# BMS-Shem-v1.net
KiCad netlist of a schematic drawn in Altium Designer
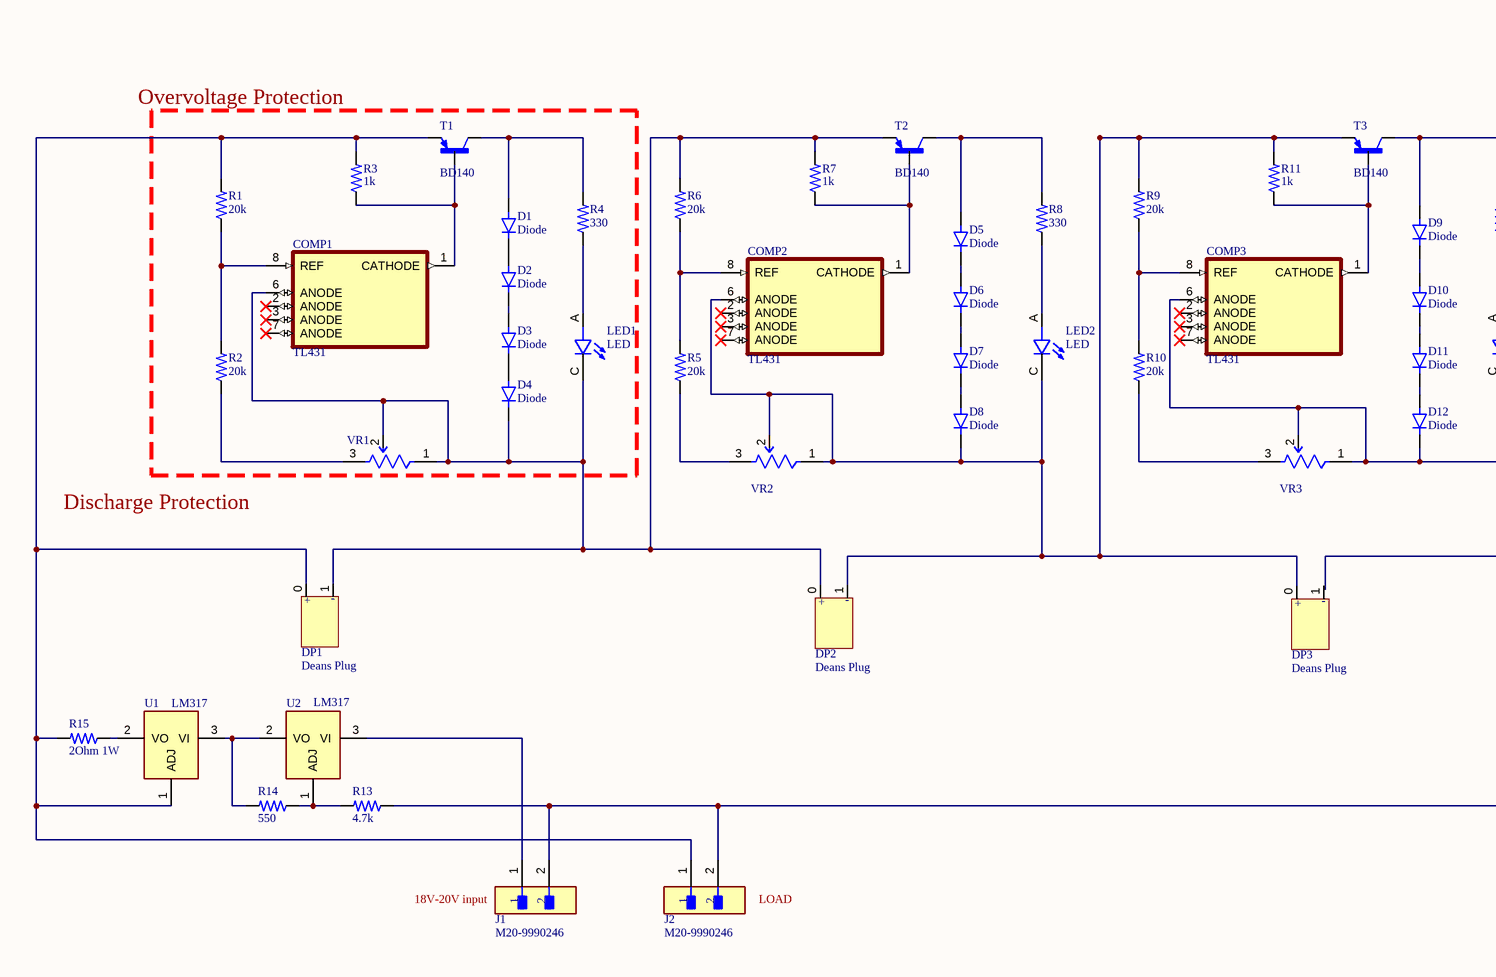
[diagram p0: BMS-Shem-v1.SchDoc, left]
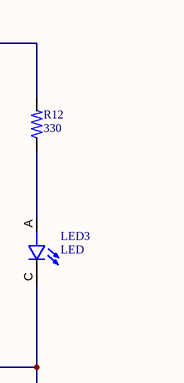
[diagram p1: BMS-Shem-v1.SchDoc, right]

(export (version "E")
  (design (tool "Eeschema 10.0.6"))
  (components
    (comp (ref "COMP1")
      (value "TL431")
      (footprint "SOIC127P599X175-8N")
      (description "Adjustable precision shunt regulator 8-SOIC 0 to 70")
      (fields (field (name "MF") "Texas Instruments") (field (name "MP") "TL431CD"))
      (libsource (lib "Schlib") (part "TL431"))
    )
    (comp (ref "COMP2")
      (value "TL431")
      (footprint "SOIC127P599X175-8N:SOIC127P599X175-8N")
      (description "Adjustable precision shunt regulator 8-SOIC 0 to 70")
      (fields (field (name "MF") "Texas Instruments") (field (name "MP") "TL431CD"))
      (libsource (lib "Schlib") (part "TL431"))
    )
    (comp (ref "COMP3")
      (value "TL431")
      (footprint "SOIC127P599X175-8N:SOIC127P599X175-8N")
      (description "Adjustable precision shunt regulator 8-SOIC 0 to 70")
      (fields (field (name "MF") "Texas Instruments") (field (name "MP") "TL431CD"))
      (libsource (lib "Schlib") (part "TL431"))
    )
    (comp (ref "D1")
      (value "Diode")
      (footprint "DIOAD1060W80L520D270")
      (description "Diode Standard 1000V 1A Through Hole DO-204AL _DO-41_")
      (fields (field (name "MF") "ON Semiconductor") (field (name "MP") "1N4007"))
      (libsource (lib "Schlib") (part "Diode"))
    )
    (comp (ref "D2")
      (value "Diode")
      (footprint "DIOAD1060W80L520D270")
      (description "Diode Standard 1000V 1A Through Hole DO-204AL _DO-41_")
      (fields (field (name "MF") "ON Semiconductor") (field (name "MP") "1N4007"))
      (libsource (lib "Schlib") (part "Diode"))
    )
    (comp (ref "D3")
      (value "Diode")
      (footprint "DIOAD1060W80L520D270")
      (description "Diode Standard 1000V 1A Through Hole DO-204AL _DO-41_")
      (fields (field (name "MF") "ON Semiconductor") (field (name "MP") "1N4007"))
      (libsource (lib "Schlib") (part "Diode"))
    )
    (comp (ref "D4")
      (value "Diode")
      (footprint "DIOAD1060W80L520D270")
      (description "Diode Standard 1000V 1A Through Hole DO-204AL _DO-41_")
      (fields (field (name "MF") "ON Semiconductor") (field (name "MP") "1N4007"))
      (libsource (lib "Schlib") (part "Diode"))
    )
    (comp (ref "D5")
      (value "Diode")
      (footprint "SnapEDApcb:DIOAD1060W80L520D270")
      (description "Diode Standard 1000V 1A Through Hole DO-204AL _DO-41_")
      (fields (field (name "MF") "ON Semiconductor") (field (name "MP") "1N4007"))
      (libsource (lib "Schlib") (part "Diode"))
    )
    (comp (ref "D6")
      (value "Diode")
      (footprint "SnapEDApcb:DIOAD1060W80L520D270")
      (description "Diode Standard 1000V 1A Through Hole DO-204AL _DO-41_")
      (fields (field (name "MF") "ON Semiconductor") (field (name "MP") "1N4007"))
      (libsource (lib "Schlib") (part "Diode"))
    )
    (comp (ref "D7")
      (value "Diode")
      (footprint "SnapEDApcb:DIOAD1060W80L520D270")
      (description "Diode Standard 1000V 1A Through Hole DO-204AL _DO-41_")
      (fields (field (name "MF") "ON Semiconductor") (field (name "MP") "1N4007"))
      (libsource (lib "Schlib") (part "Diode"))
    )
    (comp (ref "D8")
      (value "Diode")
      (footprint "SnapEDApcb:DIOAD1060W80L520D270")
      (description "Diode Standard 1000V 1A Through Hole DO-204AL _DO-41_")
      (fields (field (name "MF") "ON Semiconductor") (field (name "MP") "1N4007"))
      (libsource (lib "Schlib") (part "Diode"))
    )
    (comp (ref "D9")
      (value "Diode")
      (footprint "SnapEDApcb:DIOAD1060W80L520D270")
      (description "Diode Standard 1000V 1A Through Hole DO-204AL _DO-41_")
      (fields (field (name "MF") "ON Semiconductor") (field (name "MP") "1N4007"))
      (libsource (lib "Schlib") (part "Diode"))
    )
    (comp (ref "D10")
      (value "Diode")
      (footprint "SnapEDApcb:DIOAD1060W80L520D270")
      (description "Diode Standard 1000V 1A Through Hole DO-204AL _DO-41_")
      (fields (field (name "MF") "ON Semiconductor") (field (name "MP") "1N4007"))
      (libsource (lib "Schlib") (part "Diode"))
    )
    (comp (ref "D11")
      (value "Diode")
      (footprint "SnapEDApcb:DIOAD1060W80L520D270")
      (description "Diode Standard 1000V 1A Through Hole DO-204AL _DO-41_")
      (fields (field (name "MF") "ON Semiconductor") (field (name "MP") "1N4007"))
      (libsource (lib "Schlib") (part "Diode"))
    )
    (comp (ref "D12")
      (value "Diode")
      (footprint "SnapEDApcb:DIOAD1060W80L520D270")
      (description "Diode Standard 1000V 1A Through Hole DO-204AL _DO-41_")
      (fields (field (name "MF") "ON Semiconductor") (field (name "MP") "1N4007"))
      (libsource (lib "Schlib") (part "Diode"))
    )
    (comp (ref "DP1") (value "Deans Plug") (libsource (lib "Schlib") (part "Deans Plug")))
    (comp (ref "DP2") (value "Deans Plug") (libsource (lib "Schlib") (part "Deans Plug")))
    (comp (ref "DP3") (value "Deans Plug") (libsource (lib "Schlib") (part "Deans Plug")))
    (comp (ref "J1")
      (value "M20-9990246")
      (footprint "FP-M20-9990246-MFG")
      (description "CONN HEADER VERT 2POS 2.54MM")
      (fields
        (field (name "OCTOPART") "https://octopart.com/m20-9990246-harwin-2590635")
        (field (name "MANUFACTURER") "Harwin")
      )
      (libsource (lib "Altium Content Vault") (part "3bc925449376181038e59eaffc5286c"))
    )
    (comp (ref "J2")
      (value "M20-9990246")
      (footprint "FP-M20-9990246-MFG")
      (description "CONN HEADER VERT 2POS 2.54MM")
      (fields
        (field (name "OCTOPART") "https://octopart.com/m20-9990246-harwin-2590635")
        (field (name "MANUFACTURER") "Harwin")
      )
      (libsource (lib "Altium Content Vault") (part "3bc925449376181038e59eaffc5286c"))
    )
    (comp (ref "LED1")
      (value "LED")
      (footprint "SnapEDApcb:LED_151054RS03000")
      (description "Red 623nm LED Indication - Discrete 1.9V Radial")
      (fields (field (name "MF") "Wurth Electronics") (field (name "MP") "151054RS03000"))
      (libsource (lib "Schlib") (part "LED"))
    )
    (comp (ref "LED2")
      (value "LED")
      (footprint "SnapEDApcb:LED_151054RS03000")
      (description "Red 623nm LED Indication - Discrete 1.9V Radial")
      (fields (field (name "MF") "Wurth Electronics") (field (name "MP") "151054RS03000"))
      (libsource (lib "Schlib") (part "LED"))
    )
    (comp (ref "LED3")
      (value "LED")
      (footprint "SnapEDApcb:LED_151054RS03000")
      (description "Red 623nm LED Indication - Discrete 1.9V Radial")
      (fields (field (name "MF") "Wurth Electronics") (field (name "MP") "151054RS03000"))
      (libsource (lib "Schlib") (part "LED"))
    )
    (comp (ref "R1")
      (value "20k")
      (footprint "RESC2012X65N")
      (description "RES 20k OHM 1% 1/4W 0805")
      (fields (field (name "MF") "TE Connectivity") (field (name "TOLERANCE") "1%"))
      (libsource (lib "Schlib") (part "Resistor"))
    )
    (comp (ref "R2")
      (value "20k")
      (footprint "RESC2012X65N")
      (description "RES 20k OHM 1% 1/4W 0805")
      (fields (field (name "MF") "TE Connectivity") (field (name "TOLERANCE") "1%"))
      (libsource (lib "Schlib") (part "Resistor"))
    )
    (comp (ref "R3")
      (value "1k")
      (footprint "RESC2012X65N")
      (description "RES 1k OHM 1% 1/4W 0805")
      (fields (field (name "MF") "TE Connectivity") (field (name "TOLERANCE") "1%"))
      (libsource (lib "Schlib") (part "Resistor"))
    )
    (comp (ref "R4")
      (value "330")
      (footprint "SnapEDApcb:RESC2012X65N")
      (description "RES 330 OHM 1% 1/4W 0805")
      (fields (field (name "MF") "TE Connectivity") (field (name "TOLERANCE") "1%"))
      (libsource (lib "Schlib") (part "Resistor"))
    )
    (comp (ref "R5")
      (value "20k")
      (footprint "RESC2012X65N")
      (description "RES 20k OHM 1% 1/4W 0805")
      (fields (field (name "MF") "TE Connectivity") (field (name "TOLERANCE") "1%"))
      (libsource (lib "Schlib") (part "Resistor"))
    )
    (comp (ref "R6")
      (value "20k")
      (footprint "RESC2012X65N")
      (description "RES 20k OHM 1% 1/4W 0805")
      (fields (field (name "MF") "TE Connectivity") (field (name "TOLERANCE") "1%"))
      (libsource (lib "Schlib") (part "Resistor"))
    )
    (comp (ref "R7")
      (value "1k")
      (footprint "RESC2012X65N")
      (description "RES 1k OHM 1% 1/4W 0805")
      (fields (field (name "MF") "TE Connectivity") (field (name "TOLERANCE") "1%"))
      (libsource (lib "Schlib") (part "Resistor"))
    )
    (comp (ref "R8")
      (value "330")
      (footprint "SnapEDApcb:RESC2012X65N")
      (description "RES 330 OHM 1% 1/4W 0805")
      (fields (field (name "MF") "TE Connectivity") (field (name "TOLERANCE") "1%"))
      (libsource (lib "Schlib") (part "Resistor"))
    )
    (comp (ref "R9")
      (value "20k")
      (footprint "RESC2012X65N")
      (description "RES 20k OHM 1% 1/4W 0805")
      (fields (field (name "MF") "TE Connectivity") (field (name "TOLERANCE") "1%"))
      (libsource (lib "Schlib") (part "Resistor"))
    )
    (comp (ref "R10")
      (value "20k")
      (footprint "RESC2012X65N")
      (description "RES 20k OHM 1% 1/4W 0805")
      (fields (field (name "MF") "TE Connectivity") (field (name "TOLERANCE") "1%"))
      (libsource (lib "Schlib") (part "Resistor"))
    )
    (comp (ref "R11")
      (value "1k")
      (footprint "RESC2012X65N")
      (description "RES 1k OHM 1% 1/4W 0805")
      (fields (field (name "MF") "TE Connectivity") (field (name "TOLERANCE") "1%"))
      (libsource (lib "Schlib") (part "Resistor"))
    )
    (comp (ref "R12")
      (value "330")
      (footprint "SnapEDApcb:RESC2012X65N")
      (description "RES 330 OHM 1% 1/4W 0805")
      (fields (field (name "MF") "TE Connectivity") (field (name "TOLERANCE") "1%"))
      (libsource (lib "Schlib") (part "Resistor"))
    )
    (comp (ref "R13")
      (value "4.7k")
      (footprint "SnapEDApcb:RESC2012X65N")
      (description "RES 4.7k OHM 1% 1/4W 0805")
      (fields (field (name "MF") "TE Connectivity") (field (name "TOLERANCE") "1%"))
      (libsource (lib "Schlib") (part "Resistor"))
    )
    (comp (ref "R14")
      (value "550")
      (footprint "SnapEDApcb:RESC2012X65N")
      (description "RES 550 OHM 1% 1/4W 0805")
      (fields (field (name "MF") "TE Connectivity") (field (name "TOLERANCE") "1%"))
      (libsource (lib "Schlib") (part "Resistor"))
    )
    (comp (ref "R15")
      (value "2Ohm 1W")
      (footprint "SnapEDApcb:RESC2012X65N")
      (description "RES 2 OHM 1% 1/4W 0805")
      (fields (field (name "MF") "TE Connectivity") (field (name "TOLERANCE") "1%"))
      (libsource (lib "Schlib") (part "Resistor"))
    )
    (comp (ref "T1")
      (value "BD140")
      (footprint "SnapEDApcb:TO245P780X300X1364-3")
      (description "Bipolar _BJT_ Transistor PNP 80V 1.5A 1.25W Through Hole SOT-32-3")
      (fields (field (name "MF") "STMicroelectronics"))
      (libsource (lib "Schlib") (part "BD140"))
    )
    (comp (ref "T2")
      (value "BD140")
      (footprint "SnapEDApcb:TO245P780X300X1364-3")
      (description "Bipolar _BJT_ Transistor PNP 80V 1.5A 1.25W Through Hole SOT-32-3")
      (fields (field (name "MF") "STMicroelectronics"))
      (libsource (lib "Schlib") (part "BD140"))
    )
    (comp (ref "T3")
      (value "BD140")
      (footprint "SnapEDApcb:TO245P780X300X1364-3")
      (description "Bipolar _BJT_ Transistor PNP 80V 1.5A 1.25W Through Hole SOT-32-3")
      (fields (field (name "MF") "STMicroelectronics"))
      (libsource (lib "Schlib") (part "BD140"))
    )
    (comp (ref "U1")
      (value "LM317")
      (footprint "SnapEDApcb:TO-220")
      (description "Linear Voltage Regulator IC 1 Output 100mA SOT-89-3")
      (fields (field (name "MF") "ON Semiconductor"))
      (libsource (lib "SnapEDAsch") (part "LM317"))
    )
    (comp (ref "U2")
      (value "LM317")
      (footprint "SnapEDApcb:TO-220")
      (description "Linear Voltage Regulator IC 1 Output 100mA SOT-89-3")
      (fields (field (name "MF") "ON Semiconductor"))
      (libsource (lib "SnapEDAsch") (part "LM317"))
    )
    (comp (ref "VR1")
      (value "Res_Bourns_3296W-1-502LF_eec")
      (footprint "Bourns_3296W-1-502LF_0")
      (description "RES TRIMMER 5K OHM 0.5W PC PIN")
      (fields (field (name "PART NUMBER") "3296W-1-502LF") (field (name "MANUFACTURER") "Bourns"))
      (libsource (lib "Schlib") (part "Res_Bourns_3296W-1-502LF_eec"))
    )
    (comp (ref "VR2")
      (value "Res_Bourns_3296W-1-502LF_eec")
      (footprint "Bourns_3296W-1-502LF_0")
      (description "RES TRIMMER 5K OHM 0.5W PC PIN")
      (fields (field (name "PART NUMBER") "3296W-1-502LF") (field (name "MANUFACTURER") "Bourns"))
      (libsource (lib "Schlib") (part "Res_Bourns_3296W-1-502LF_eec"))
    )
    (comp (ref "VR3")
      (value "Res_Bourns_3296W-1-502LF_eec")
      (footprint "Bourns_3296W-1-502LF_0")
      (description "RES TRIMMER 5K OHM 0.5W PC PIN")
      (fields (field (name "PART NUMBER") "3296W-1-502LF") (field (name "MANUFACTURER") "Bourns"))
      (libsource (lib "Schlib") (part "Res_Bourns_3296W-1-502LF_eec"))
    )
  )
  (nets
    (net (code "1") (name "Net-(COMP1-CATHODE)") (class "Default")
      (node (ref "COMP1") (pin "1") (pinfunction "CATHODE_1") (pintype "output"))
      (node (ref "R3") (pin "1") (pinfunction "1_1") (pintype "passive"))
      (node (ref "T1") (pin "3") (pinfunction "B_3") (pintype "passive"))
    )
    (net (code "2") (name "Net-(COMP1-REF)") (class "Default")
      (node (ref "COMP1") (pin "8") (pinfunction "REF_8") (pintype "input"))
      (node (ref "R1") (pin "1") (pinfunction "1_1") (pintype "passive"))
      (node (ref "R2") (pin "2") (pinfunction "2_2") (pintype "passive"))
    )
    (net (code "3") (name "Net-(COMP2-CATHODE)") (class "Default")
      (node (ref "COMP2") (pin "1") (pinfunction "CATHODE_1") (pintype "output"))
      (node (ref "R7") (pin "1") (pinfunction "1_1") (pintype "passive"))
      (node (ref "T2") (pin "3") (pinfunction "B_3") (pintype "passive"))
    )
    (net (code "4") (name "Net-(COMP2-REF)") (class "Default")
      (node (ref "COMP2") (pin "8") (pinfunction "REF_8") (pintype "input"))
      (node (ref "R5") (pin "2") (pinfunction "2_2") (pintype "passive"))
      (node (ref "R6") (pin "1") (pinfunction "1_1") (pintype "passive"))
    )
    (net (code "5") (name "Net-(COMP3-CATHODE)") (class "Default")
      (node (ref "COMP3") (pin "1") (pinfunction "CATHODE_1") (pintype "output"))
      (node (ref "R11") (pin "1") (pinfunction "1_1") (pintype "passive"))
      (node (ref "T3") (pin "3") (pinfunction "B_3") (pintype "passive"))
    )
    (net (code "6") (name "Net-(COMP3-REF)") (class "Default")
      (node (ref "COMP3") (pin "8") (pinfunction "REF_8") (pintype "input"))
      (node (ref "R10") (pin "2") (pinfunction "2_2") (pintype "passive"))
      (node (ref "R9") (pin "1") (pinfunction "1_1") (pintype "passive"))
    )
    (net (code "7") (name "Net-(D1-PadC)") (class "Default")
      (node (ref "D1") (pin "C") (pinfunction "C_C") (pintype "passive"))
      (node (ref "D2") (pin "A") (pinfunction "A_A") (pintype "passive"))
    )
    (net (code "8") (name "Net-(D2-PadC)") (class "Default")
      (node (ref "D2") (pin "C") (pinfunction "C_C") (pintype "passive"))
      (node (ref "D3") (pin "A") (pinfunction "A_A") (pintype "passive"))
    )
    (net (code "9") (name "Net-(D3-PadC)") (class "Default")
      (node (ref "D3") (pin "C") (pinfunction "C_C") (pintype "passive"))
      (node (ref "D4") (pin "A") (pinfunction "A_A") (pintype "passive"))
    )
    (net (code "10") (name "Net-(D5-PadC)") (class "Default")
      (node (ref "D5") (pin "C") (pinfunction "C_C") (pintype "passive"))
      (node (ref "D6") (pin "A") (pinfunction "A_A") (pintype "passive"))
    )
    (net (code "11") (name "Net-(D6-PadC)") (class "Default")
      (node (ref "D6") (pin "C") (pinfunction "C_C") (pintype "passive"))
      (node (ref "D7") (pin "A") (pinfunction "A_A") (pintype "passive"))
    )
    (net (code "12") (name "Net-(D7-PadC)") (class "Default")
      (node (ref "D7") (pin "C") (pinfunction "C_C") (pintype "passive"))
      (node (ref "D8") (pin "A") (pinfunction "A_A") (pintype "passive"))
    )
    (net (code "13") (name "Net-(D10-PadA)") (class "Default")
      (node (ref "D10") (pin "A") (pinfunction "A_A") (pintype "passive"))
      (node (ref "D9") (pin "C") (pinfunction "C_C") (pintype "passive"))
    )
    (net (code "14") (name "Net-(D10-PadC)") (class "Default")
      (node (ref "D10") (pin "C") (pinfunction "C_C") (pintype "passive"))
      (node (ref "D11") (pin "A") (pinfunction "A_A") (pintype "passive"))
    )
    (net (code "15") (name "Net-(D11-PadC)") (class "Default")
      (node (ref "D11") (pin "C") (pinfunction "C_C") (pintype "passive"))
      (node (ref "D12") (pin "A") (pinfunction "A_A") (pintype "passive"))
    )
    (net (code "16") (name "Net-(LED1-PadA)") (class "Default")
      (node (ref "LED1") (pin "A") (pinfunction "A_A") (pintype "passive"))
      (node (ref "R4") (pin "1") (pinfunction "1_1") (pintype "passive"))
    )
    (net (code "17") (name "Net-(LED2-PadA)") (class "Default")
      (node (ref "LED2") (pin "A") (pinfunction "A_A") (pintype "passive"))
      (node (ref "R8") (pin "1") (pinfunction "1_1") (pintype "passive"))
    )
    (net (code "18") (name "Net-(LED3-PadA)") (class "Default")
      (node (ref "LED3") (pin "A") (pinfunction "A_A") (pintype "passive"))
      (node (ref "R12") (pin "1") (pinfunction "1_1") (pintype "passive"))
    )
    (net (code "19") (name "Net-(T1-C)") (class "Default")
      (node (ref "D1") (pin "A") (pinfunction "A_A") (pintype "passive"))
      (node (ref "R4") (pin "2") (pinfunction "2_2") (pintype "passive"))
      (node (ref "T1") (pin "2") (pinfunction "C_2") (pintype "passive"))
    )
    (net (code "20") (name "Net-(T1-E)") (class "Default")
      (node (ref "DP1") (pin "0") (pinfunction "0_0") (pintype "passive"))
      (node (ref "J2") (pin "1") (pinfunction "1_1") (pintype "passive"))
      (node (ref "R1") (pin "2") (pinfunction "2_2") (pintype "passive"))
      (node (ref "R15") (pin "2") (pinfunction "2_2") (pintype "passive"))
      (node (ref "R3") (pin "2") (pinfunction "2_2") (pintype "passive"))
      (node (ref "T1") (pin "1") (pinfunction "E_1") (pintype "passive"))
      (node (ref "U1") (pin "1") (pinfunction "ADJ_1") (pintype "power_in"))
    )
    (net (code "21") (name "Net-(T2-C)") (class "Default")
      (node (ref "D5") (pin "A") (pinfunction "A_A") (pintype "passive"))
      (node (ref "R8") (pin "2") (pinfunction "2_2") (pintype "passive"))
      (node (ref "T2") (pin "2") (pinfunction "C_2") (pintype "passive"))
    )
    (net (code "22") (name "Net-(T2-E)") (class "Default")
      (node (ref "COMP1") (pin "6") (pinfunction "ANODE_6") (pintype "bidirectional"))
      (node (ref "D4") (pin "C") (pinfunction "C_C") (pintype "passive"))
      (node (ref "DP1") (pin "1") (pinfunction "1_1") (pintype "passive"))
      (node (ref "DP2") (pin "0") (pinfunction "0_0") (pintype "passive"))
      (node (ref "LED1") (pin "C") (pinfunction "C_C") (pintype "passive"))
      (node (ref "R6") (pin "2") (pinfunction "2_2") (pintype "passive"))
      (node (ref "R7") (pin "2") (pinfunction "2_2") (pintype "passive"))
      (node (ref "T2") (pin "1") (pinfunction "E_1") (pintype "passive"))
      (node (ref "VR1") (pin "1") (pinfunction "CCW_1") (pintype "passive"))
      (node (ref "VR1") (pin "2") (pinfunction "WIPER_2") (pintype "passive"))
    )
    (net (code "23") (name "Net-(T3-C)") (class "Default")
      (node (ref "D9") (pin "A") (pinfunction "A_A") (pintype "passive"))
      (node (ref "R12") (pin "2") (pinfunction "2_2") (pintype "passive"))
      (node (ref "T3") (pin "2") (pinfunction "C_2") (pintype "passive"))
    )
    (net (code "24") (name "Net-(T3-E)") (class "Default")
      (node (ref "COMP2") (pin "6") (pinfunction "ANODE_6") (pintype "bidirectional"))
      (node (ref "D8") (pin "C") (pinfunction "C_C") (pintype "passive"))
      (node (ref "DP2") (pin "1") (pinfunction "1_1") (pintype "passive"))
      (node (ref "DP3") (pin "0") (pinfunction "0_0") (pintype "passive"))
      (node (ref "LED2") (pin "C") (pinfunction "C_C") (pintype "passive"))
      (node (ref "R11") (pin "2") (pinfunction "2_2") (pintype "passive"))
      (node (ref "R9") (pin "2") (pinfunction "2_2") (pintype "passive"))
      (node (ref "T3") (pin "1") (pinfunction "E_1") (pintype "passive"))
      (node (ref "VR2") (pin "1") (pinfunction "CCW_1") (pintype "passive"))
      (node (ref "VR2") (pin "2") (pinfunction "WIPER_2") (pintype "passive"))
    )
    (net (code "25") (name "Net-(U1-VI)") (class "Default")
      (node (ref "R14") (pin "2") (pinfunction "2_2") (pintype "passive"))
      (node (ref "U1") (pin "3") (pinfunction "VI_3") (pintype "power_in"))
      (node (ref "U2") (pin "2") (pinfunction "VO_2") (pintype "power_in"))
    )
    (net (code "26") (name "Net-(U1-VO)") (class "Default")
      (node (ref "R15") (pin "1") (pinfunction "1_1") (pintype "passive"))
      (node (ref "U1") (pin "2") (pinfunction "VO_2") (pintype "power_in"))
    )
    (net (code "27") (name "Net-(U2-ADJ)") (class "Default")
      (node (ref "R13") (pin "2") (pinfunction "2_2") (pintype "passive"))
      (node (ref "R14") (pin "1") (pinfunction "1_1") (pintype "passive"))
      (node (ref "U2") (pin "1") (pinfunction "ADJ_1") (pintype "power_in"))
    )
    (net (code "28") (name "Net-(U2-VI)") (class "Default")
      (node (ref "J1") (pin "1") (pinfunction "1_1") (pintype "passive"))
      (node (ref "U2") (pin "3") (pinfunction "VI_3") (pintype "power_in"))
    )
    (net (code "29") (name "Net-(VR1-CW)") (class "Default")
      (node (ref "R2") (pin "1") (pinfunction "1_1") (pintype "passive"))
      (node (ref "VR1") (pin "3") (pinfunction "CW_3") (pintype "passive"))
    )
    (net (code "30") (name "Net-(VR2-CW)") (class "Default")
      (node (ref "R5") (pin "1") (pinfunction "1_1") (pintype "passive"))
      (node (ref "VR2") (pin "3") (pinfunction "CW_3") (pintype "passive"))
    )
    (net (code "31") (name "Net-(VR3-CCW)") (class "Default")
      (node (ref "COMP3") (pin "6") (pinfunction "ANODE_6") (pintype "bidirectional"))
      (node (ref "D12") (pin "C") (pinfunction "C_C") (pintype "passive"))
      (node (ref "J1") (pin "2") (pinfunction "2_2") (pintype "passive"))
      (node (ref "J2") (pin "2") (pinfunction "2_2") (pintype "passive"))
      (node (ref "LED3") (pin "C") (pinfunction "C_C") (pintype "passive"))
      (node (ref "R13") (pin "1") (pinfunction "1_1") (pintype "passive"))
      (node (ref "VR3") (pin "1") (pinfunction "CCW_1") (pintype "passive"))
      (node (ref "VR3") (pin "2") (pinfunction "WIPER_2") (pintype "passive"))
    )
    (net (code "32") (name "Net-(VR3-CW)") (class "Default")
      (node (ref "R10") (pin "1") (pinfunction "1_1") (pintype "passive"))
      (node (ref "VR3") (pin "3") (pinfunction "CW_3") (pintype "passive"))
    )
    (net (code "33") (name "unconnected-(COMP1-ANODE-Pad2)") (class "Default")
      (node (ref "COMP1") (pin "2") (pinfunction "ANODE_2") (pintype "bidirectional+no_connect"))
    )
    (net (code "34") (name "unconnected-(COMP1-ANODE-Pad3)") (class "Default")
      (node (ref "COMP1") (pin "3") (pinfunction "ANODE_3") (pintype "bidirectional+no_connect"))
    )
    (net (code "35") (name "unconnected-(COMP1-ANODE-Pad7)") (class "Default")
      (node (ref "COMP1") (pin "7") (pinfunction "ANODE_7") (pintype "bidirectional+no_connect"))
    )
    (net (code "36") (name "unconnected-(COMP2-ANODE-Pad2)") (class "Default")
      (node (ref "COMP2") (pin "2") (pinfunction "ANODE_2") (pintype "bidirectional+no_connect"))
    )
    (net (code "37") (name "unconnected-(COMP2-ANODE-Pad3)") (class "Default")
      (node (ref "COMP2") (pin "3") (pinfunction "ANODE_3") (pintype "bidirectional+no_connect"))
    )
    (net (code "38") (name "unconnected-(COMP2-ANODE-Pad7)") (class "Default")
      (node (ref "COMP2") (pin "7") (pinfunction "ANODE_7") (pintype "bidirectional+no_connect"))
    )
    (net (code "39") (name "unconnected-(COMP3-ANODE-Pad2)") (class "Default")
      (node (ref "COMP3") (pin "2") (pinfunction "ANODE_2") (pintype "bidirectional+no_connect"))
    )
    (net (code "40") (name "unconnected-(COMP3-ANODE-Pad3)") (class "Default")
      (node (ref "COMP3") (pin "3") (pinfunction "ANODE_3") (pintype "bidirectional+no_connect"))
    )
    (net (code "41") (name "unconnected-(COMP3-ANODE-Pad7)") (class "Default")
      (node (ref "COMP3") (pin "7") (pinfunction "ANODE_7") (pintype "bidirectional+no_connect"))
    )
    (net (code "42") (name "unconnected-(DP3-Pad1)") (class "Default")
      (node (ref "DP3") (pin "1") (pinfunction "1_1") (pintype "passive"))
    )
  )
)
